# MCU_1.net
KiCad netlist of a schematic drawn in Altium Designer
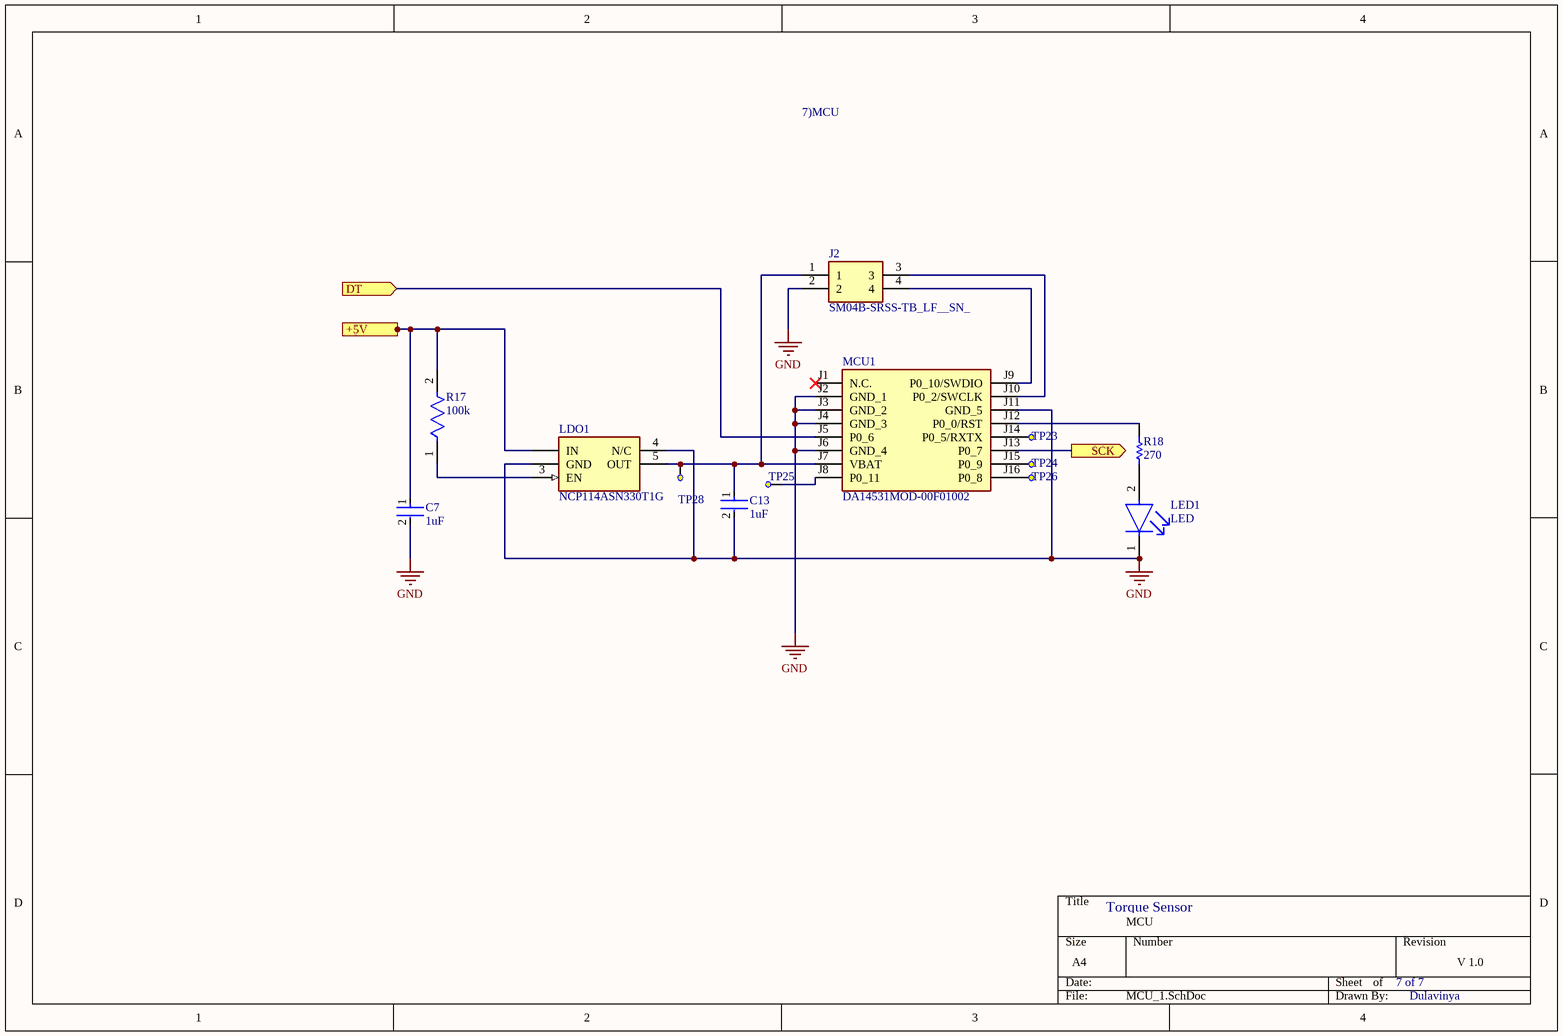
[diagram p0: MCU_1.SchDoc]

(export (version "E")
  (design (tool "Eeschema 10.0.6"))
  (components
    (comp (ref "C7")
      (value "1uF")
      (footprint "FP-C0402C105K8PACTU-MFG")
      (description "CAP CER 1UF 10V X5R 0402")
      (fields (field (name "VOLTAGE") "10V") (field (name "TOLERANCE") "10%"))
      (libsource (lib "Altium Content Vault") (part "11868f565c42a9108669ba33697ecf6"))
    )
    (comp (ref "C13")
      (value "1uF")
      (footprint "FP-C0402C105K8PACTU-MFG")
      (description "CAP CER 1UF 10V X5R 0402")
      (fields (field (name "VOLTAGE") "10V") (field (name "TOLERANCE") "10%"))
      (libsource (lib "Altium Content Vault") (part "11868f565c42a9108669ba33697ecf6"))
    )
    (comp (ref "J2")
      (value "SM04B-SRSS-TB_LF__SN_")
      (footprint "SamacSys:SM04B-SRSS-TB(LFSN)")
      (description "Connector")
      (fields
        (field (name "MANUFACTURER_PART_NUMBER") "SM04B-SRSS-TB(LF)(SN)")
        (field (name "MOUSER PART NUMBER") "306-SM04BSRSSTBLFSN")
      )
      (libsource (lib "*") (part "SM04B-SRSS-TB_LF__SN_"))
    )
    (comp (ref "LDO1")
      (value "NCP114ASN330T1G")
      (footprint "SamacSys:SOT95P275X110-5N")
      (description "Power Supply")
      (fields (field (name "MOUSER PART NUMBER") "863-NCP114ASN330T1G"))
      (libsource (lib "*") (part "NCP114ASN330T1G"))
    )
    (comp (ref "LED1")
      (value "LED")
      (footprint "FP-APHHS1005CGCK-MFG")
      (description "LED GREEN CLEAR CHIP SMD")
      (libsource (lib "Altium Content Vault") (part "8706943c75ba83719d021d2fdc84c58"))
    )
    (comp (ref "MCU1")
      (value "DA14531MOD-00F01002")
      (footprint "SamacSys:DA14531MOD00F01002")
      (description "Integrated Circuit")
      (fields (field (name "MOUSER PART NUMBER") "724-DA14531MODF01002"))
      (libsource (lib "*") (part "DA14531MOD-00F01002"))
    )
    (comp (ref "R17")
      (value "100k")
      (footprint "FP-ERJ2RK-IPC_C")
      (description "RES SMD 100K OHM 1% 1/10W 0402")
      (fields (field (name "TOLERANCE") "1%"))
      (libsource (lib "Altium Content Vault") (part "1029c3af85768c4190bb7ad29bc67b5"))
    )
    (comp (ref "R18")
      (value "270")
      (footprint "RESC1005X40X25ML05T05")
      (fields (field (name "PART NUMBER") "CRCW0402270RFKED") (field (name "MANUFACTURER") "Vishay Dale"))
      (libsource (lib "Altium Content Vault") (part "RES"))
    )
    (comp (ref "TP23")
      (value "Test point")
      (footprint "Test_point")
      (libsource (lib "Schlib1") (part "test_point"))
    )
    (comp (ref "TP24")
      (value "Test point")
      (footprint "Test_point")
      (libsource (lib "Schlib1") (part "test_point"))
    )
    (comp (ref "TP25")
      (value "Test point")
      (footprint "Test_point")
      (libsource (lib "Schlib1") (part "test_point"))
    )
    (comp (ref "TP26")
      (value "Test point")
      (footprint "Test_point")
      (libsource (lib "Schlib1") (part "test_point"))
    )
    (comp (ref "TP28")
      (value "Test point")
      (footprint "Test_point")
      (libsource (lib "Schlib1") (part "test_point"))
    )
  )
  (nets
    (net (code "1") (name "/+5V") (class "Default")
      (node (ref "C7") (pin "1") (pinfunction "1_1") (pintype "passive"))
      (node (ref "LDO1") (pin "1") (pinfunction "IN_1") (pintype "power_in"))
      (node (ref "R17") (pin "2") (pinfunction "2_2") (pintype "passive"))
    )
    (net (code "2") (name "/DT") (class "Default")
      (node (ref "MCU1") (pin "J5") (pinfunction "P0_6_J5") (pintype "passive"))
    )
    (net (code "3") (name "/SCK") (class "Default")
      (node (ref "MCU1") (pin "J13") (pinfunction "P0_7_J13") (pintype "passive"))
    )
    (net (code "4") (name "GND") (class "Default")
      (node (ref "C13") (pin "2") (pinfunction "2_2") (pintype "passive"))
      (node (ref "C7") (pin "2") (pinfunction "2_2") (pintype "passive"))
      (node (ref "J2") (pin "2") (pinfunction "2_2") (pintype "passive"))
      (node (ref "LDO1") (pin "2") (pinfunction "GND_2") (pintype "power_in"))
      (node (ref "LDO1") (pin "4") (pinfunction "N/C_4") (pintype "passive"))
      (node (ref "LED1") (pin "1") (pinfunction "C_1") (pintype "passive"))
      (node (ref "MCU1") (pin "J11") (pinfunction "GND_5_J11") (pintype "passive"))
      (node (ref "MCU1") (pin "J2") (pinfunction "GND_1_J2") (pintype "passive"))
      (node (ref "MCU1") (pin "J3") (pinfunction "GND_2_J3") (pintype "passive"))
      (node (ref "MCU1") (pin "J4") (pinfunction "GND_3_J4") (pintype "passive"))
      (node (ref "MCU1") (pin "J6") (pinfunction "GND_4_J6") (pintype "passive"))
    )
    (net (code "5") (name "Net-(LDO1-EN)") (class "Default")
      (node (ref "LDO1") (pin "3") (pinfunction "EN_3") (pintype "input"))
      (node (ref "R17") (pin "1") (pinfunction "1_1") (pintype "passive"))
    )
    (net (code "6") (name "Net-(LDO1-OUT)") (class "Default")
      (node (ref "C13") (pin "1") (pinfunction "1_1") (pintype "passive"))
      (node (ref "J2") (pin "1") (pinfunction "1_1") (pintype "passive"))
      (node (ref "LDO1") (pin "5") (pinfunction "OUT_5") (pintype "power_in"))
      (node (ref "MCU1") (pin "J7") (pinfunction "VBAT_J7") (pintype "passive"))
      (node (ref "TP28") (pin "TP?") (pinfunction "Test_point_TP?") (pintype "passive"))
    )
    (net (code "7") (name "Net-(LED1-A)") (class "Default")
      (node (ref "LED1") (pin "2") (pinfunction "A_2") (pintype "passive"))
      (node (ref "R18") (pin "2") (pinfunction "2_2") (pintype "passive"))
    )
    (net (code "8") (name "Net-(MCU1-P0_0{slash}RST)") (class "Default")
      (node (ref "MCU1") (pin "J12") (pinfunction "P0_0/RST_J12") (pintype "passive"))
      (node (ref "R18") (pin "1") (pinfunction "1_1") (pintype "passive"))
    )
    (net (code "9") (name "Net-(MCU1-P0_2{slash}SWCLK)") (class "Default")
      (node (ref "J2") (pin "3") (pinfunction "3_3") (pintype "passive"))
      (node (ref "MCU1") (pin "J10") (pinfunction "P0_2/SWCLK_J10") (pintype "passive"))
    )
    (net (code "10") (name "Net-(MCU1-P0_5{slash}RXTX)") (class "Default")
      (node (ref "MCU1") (pin "J14") (pinfunction "P0_5/RXTX_J14") (pintype "passive"))
      (node (ref "TP23") (pin "TP?") (pinfunction "Test_point_TP?") (pintype "passive"))
    )
    (net (code "11") (name "Net-(MCU1-P0_8)") (class "Default")
      (node (ref "MCU1") (pin "J16") (pinfunction "P0_8_J16") (pintype "passive"))
      (node (ref "TP26") (pin "TP?") (pinfunction "Test_point_TP?") (pintype "passive"))
    )
    (net (code "12") (name "Net-(MCU1-P0_9)") (class "Default")
      (node (ref "MCU1") (pin "J15") (pinfunction "P0_9_J15") (pintype "passive"))
      (node (ref "TP24") (pin "TP?") (pinfunction "Test_point_TP?") (pintype "passive"))
    )
    (net (code "13") (name "Net-(MCU1-P0_10{slash}SWDIO)") (class "Default")
      (node (ref "J2") (pin "4") (pinfunction "4_4") (pintype "passive"))
      (node (ref "MCU1") (pin "J9") (pinfunction "P0_10/SWDIO_J9") (pintype "passive"))
    )
    (net (code "14") (name "Net-(MCU1-P0_11)") (class "Default")
      (node (ref "MCU1") (pin "J8") (pinfunction "P0_11_J8") (pintype "passive"))
      (node (ref "TP25") (pin "TP?") (pinfunction "Test_point_TP?") (pintype "passive"))
    )
    (net (code "15") (name "unconnected-(MCU1-N.C.-PadJ1)") (class "Default")
      (node (ref "MCU1") (pin "J1") (pinfunction "N.C._J1") (pintype "passive+no_connect"))
    )
  )
)
